# dials.net
KiCad netlist of a schematic drawn in EAGLE
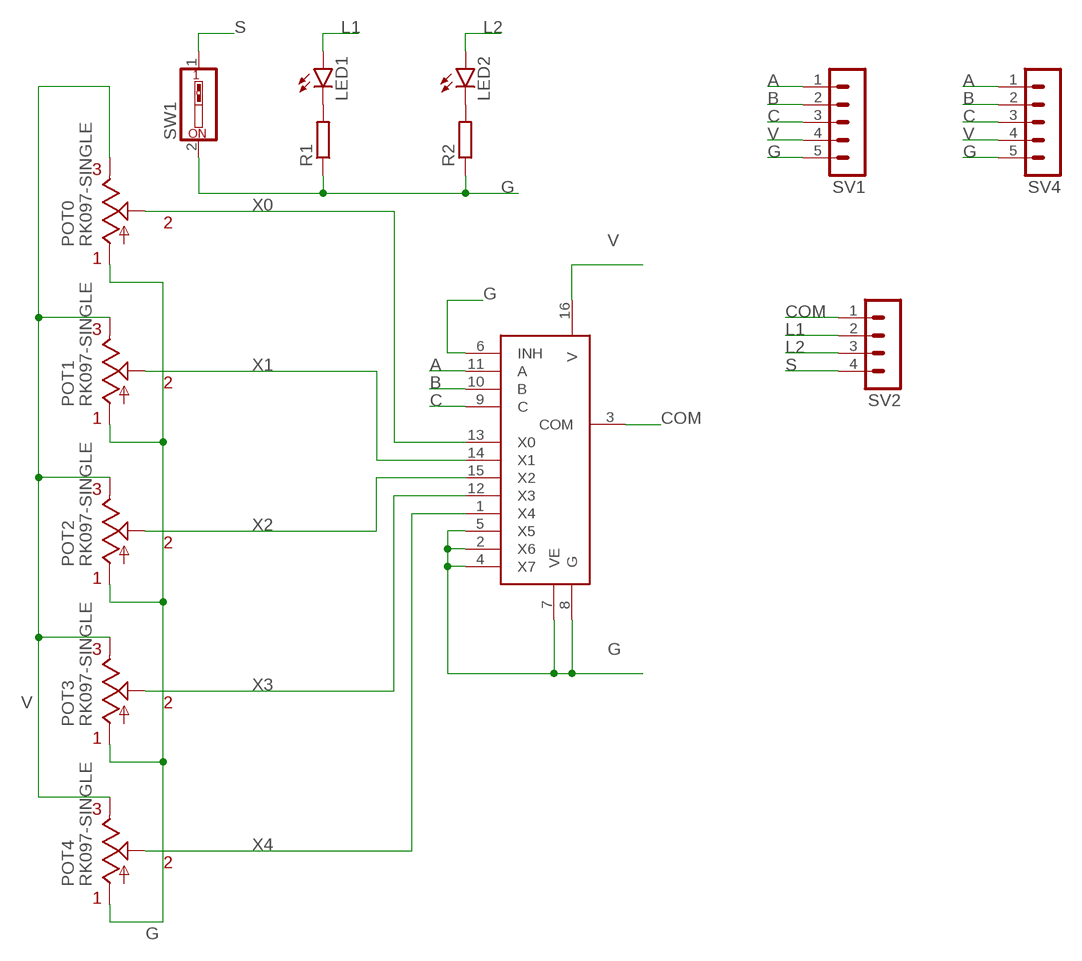
[diagram p0: schematic, sheet 1]

(export (version "E")
  (design (tool "Eeschema 10.0.6"))
  (components
    (comp (ref "LED1")
      (value "LED3MM")
      (footprint "eagle-import:LED3MM")
      (libsource (lib "eagle-import") (part "LED3MM"))
    )
    (comp (ref "LED2")
      (value "LED3MM")
      (footprint "eagle-import:LED3MM")
      (libsource (lib "eagle-import") (part "LED3MM"))
    )
    (comp (ref "POT0")
      (value "RK097-SINGLE")
      (footprint "eagle-import:RK097-SINGLE-ELEMENT")
      (libsource (lib "eagle-import") (part "RK097-SINGLE"))
    )
    (comp (ref "POT1")
      (value "RK097-SINGLE")
      (footprint "eagle-import:RK097-SINGLE-ELEMENT")
      (libsource (lib "eagle-import") (part "RK097-SINGLE"))
    )
    (comp (ref "POT2")
      (value "RK097-SINGLE")
      (footprint "eagle-import:RK097-SINGLE-ELEMENT")
      (libsource (lib "eagle-import") (part "RK097-SINGLE"))
    )
    (comp (ref "POT3")
      (value "RK097-SINGLE")
      (footprint "eagle-import:RK097-SINGLE-ELEMENT")
      (libsource (lib "eagle-import") (part "RK097-SINGLE"))
    )
    (comp (ref "POT4")
      (value "RK097-SINGLE")
      (footprint "eagle-import:RK097-SINGLE-ELEMENT")
      (libsource (lib "eagle-import") (part "RK097-SINGLE"))
    )
    (comp (ref "R1")
      (value "R-EU_0204/7")
      (footprint "eagle-import:0204_7")
      (libsource (lib "eagle-import") (part "R-EU_0204/7"))
    )
    (comp (ref "R2")
      (value "R-EU_0204/7")
      (footprint "eagle-import:0204_7")
      (libsource (lib "eagle-import") (part "R-EU_0204/7"))
    )
    (comp (ref "SV1")
      (value "MA05-1")
      (footprint "eagle-import:MA05-1")
      (libsource (lib "eagle-import") (part "MA05-1"))
    )
    (comp (ref "SV2")
      (value "MA04-1")
      (footprint "eagle-import:MA04-1")
      (libsource (lib "eagle-import") (part "MA04-1"))
    )
    (comp (ref "SV4")
      (value "MA05-1")
      (footprint "eagle-import:MA05-1")
      (libsource (lib "eagle-import") (part "MA05-1"))
    )
    (comp (ref "SW1")
      (value "SW_DIP-1")
      (footprint "eagle-import:EDG-01")
      (libsource (lib "eagle-import") (part "SW_DIP-1"))
    )
    (comp (ref "U$6")
      (value "MC14051")
      (footprint "eagle-import:DIP16")
      (libsource (lib "eagle-import") (part "MC14051"))
    )
  )
  (nets
    (net (code "1") (name "/A") (class "Default")
      (node (ref "SV1") (pin "1") (pinfunction "1_1") (pintype "passive"))
      (node (ref "SV4") (pin "1") (pinfunction "1_1") (pintype "passive"))
      (node (ref "U$6") (pin "11") (pinfunction "A_11") (pintype "bidirectional"))
    )
    (net (code "2") (name "/B") (class "Default")
      (node (ref "SV1") (pin "2") (pinfunction "2_2") (pintype "passive"))
      (node (ref "SV4") (pin "2") (pinfunction "2_2") (pintype "passive"))
      (node (ref "U$6") (pin "10") (pinfunction "B_10") (pintype "bidirectional"))
    )
    (net (code "3") (name "/C") (class "Default")
      (node (ref "SV1") (pin "3") (pinfunction "3_3") (pintype "passive"))
      (node (ref "SV4") (pin "3") (pinfunction "3_3") (pintype "passive"))
      (node (ref "U$6") (pin "9") (pinfunction "C_9") (pintype "bidirectional"))
    )
    (net (code "4") (name "/COM") (class "Default")
      (node (ref "SV2") (pin "1") (pinfunction "1_1") (pintype "passive"))
      (node (ref "U$6") (pin "3") (pinfunction "COM_3") (pintype "bidirectional"))
    )
    (net (code "5") (name "/G") (class "Default")
      (node (ref "POT0") (pin "P$4") (pinfunction "A_P$4") (pintype "passive"))
      (node (ref "POT1") (pin "P$4") (pinfunction "A_P$4") (pintype "passive"))
      (node (ref "POT2") (pin "P$4") (pinfunction "A_P$4") (pintype "passive"))
      (node (ref "POT3") (pin "P$4") (pinfunction "A_P$4") (pintype "passive"))
      (node (ref "POT4") (pin "P$4") (pinfunction "A_P$4") (pintype "passive"))
      (node (ref "R1") (pin "1") (pinfunction "1_1") (pintype "passive"))
      (node (ref "R2") (pin "1") (pinfunction "1_1") (pintype "passive"))
      (node (ref "SV1") (pin "5") (pinfunction "5_5") (pintype "passive"))
      (node (ref "SV4") (pin "5") (pinfunction "5_5") (pintype "passive"))
      (node (ref "SW1") (pin "2") (pinfunction "2_2") (pintype "passive"))
      (node (ref "U$6") (pin "2") (pinfunction "X6_2") (pintype "bidirectional"))
      (node (ref "U$6") (pin "4") (pinfunction "X7_4") (pintype "bidirectional"))
      (node (ref "U$6") (pin "5") (pinfunction "X5_5") (pintype "bidirectional"))
      (node (ref "U$6") (pin "6") (pinfunction "INH_6") (pintype "bidirectional"))
      (node (ref "U$6") (pin "7") (pinfunction "VE_7") (pintype "bidirectional"))
      (node (ref "U$6") (pin "8") (pinfunction "G_8") (pintype "bidirectional"))
    )
    (net (code "6") (name "/L1") (class "Default")
      (node (ref "LED1") (pin "A") (pinfunction "A_A") (pintype "passive"))
      (node (ref "SV2") (pin "2") (pinfunction "2_2") (pintype "passive"))
    )
    (net (code "7") (name "/L2") (class "Default")
      (node (ref "LED2") (pin "A") (pinfunction "A_A") (pintype "passive"))
      (node (ref "SV2") (pin "3") (pinfunction "3_3") (pintype "passive"))
    )
    (net (code "8") (name "/S") (class "Default")
      (node (ref "SV2") (pin "4") (pinfunction "4_4") (pintype "passive"))
      (node (ref "SW1") (pin "1") (pinfunction "1_1") (pintype "passive"))
    )
    (net (code "9") (name "/V") (class "Default")
      (node (ref "POT0") (pin "P$6") (pinfunction "E_P$6") (pintype "passive"))
      (node (ref "POT1") (pin "P$6") (pinfunction "E_P$6") (pintype "passive"))
      (node (ref "POT2") (pin "P$6") (pinfunction "E_P$6") (pintype "passive"))
      (node (ref "POT3") (pin "P$6") (pinfunction "E_P$6") (pintype "passive"))
      (node (ref "POT4") (pin "P$6") (pinfunction "E_P$6") (pintype "passive"))
      (node (ref "SV1") (pin "4") (pinfunction "4_4") (pintype "passive"))
      (node (ref "SV4") (pin "4") (pinfunction "4_4") (pintype "passive"))
      (node (ref "U$6") (pin "16") (pinfunction "V_16") (pintype "bidirectional"))
    )
    (net (code "10") (name "/X0") (class "Default")
      (node (ref "POT0") (pin "P$5") (pinfunction "S_P$5") (pintype "passive"))
      (node (ref "U$6") (pin "13") (pinfunction "X0_13") (pintype "bidirectional"))
    )
    (net (code "11") (name "/X1") (class "Default")
      (node (ref "POT1") (pin "P$5") (pinfunction "S_P$5") (pintype "passive"))
      (node (ref "U$6") (pin "14") (pinfunction "X1_14") (pintype "bidirectional"))
    )
    (net (code "12") (name "/X2") (class "Default")
      (node (ref "POT2") (pin "P$5") (pinfunction "S_P$5") (pintype "passive"))
      (node (ref "U$6") (pin "15") (pinfunction "X2_15") (pintype "bidirectional"))
    )
    (net (code "13") (name "/X3") (class "Default")
      (node (ref "POT3") (pin "P$5") (pinfunction "S_P$5") (pintype "passive"))
      (node (ref "U$6") (pin "12") (pinfunction "X3_12") (pintype "bidirectional"))
    )
    (net (code "14") (name "/X4") (class "Default")
      (node (ref "POT4") (pin "P$5") (pinfunction "S_P$5") (pintype "passive"))
      (node (ref "U$6") (pin "1") (pinfunction "X4_1") (pintype "bidirectional"))
    )
    (net (code "15") (name "Net-(LED1-C)") (class "Default")
      (node (ref "LED1") (pin "K") (pinfunction "C_K") (pintype "passive"))
      (node (ref "R1") (pin "2") (pinfunction "2_2") (pintype "passive"))
    )
    (net (code "16") (name "Net-(LED2-C)") (class "Default")
      (node (ref "LED2") (pin "K") (pinfunction "C_K") (pintype "passive"))
      (node (ref "R2") (pin "2") (pinfunction "2_2") (pintype "passive"))
    )
  )
)
